# MainPSU.net
KiCad netlist of a schematic drawn in EAGLE
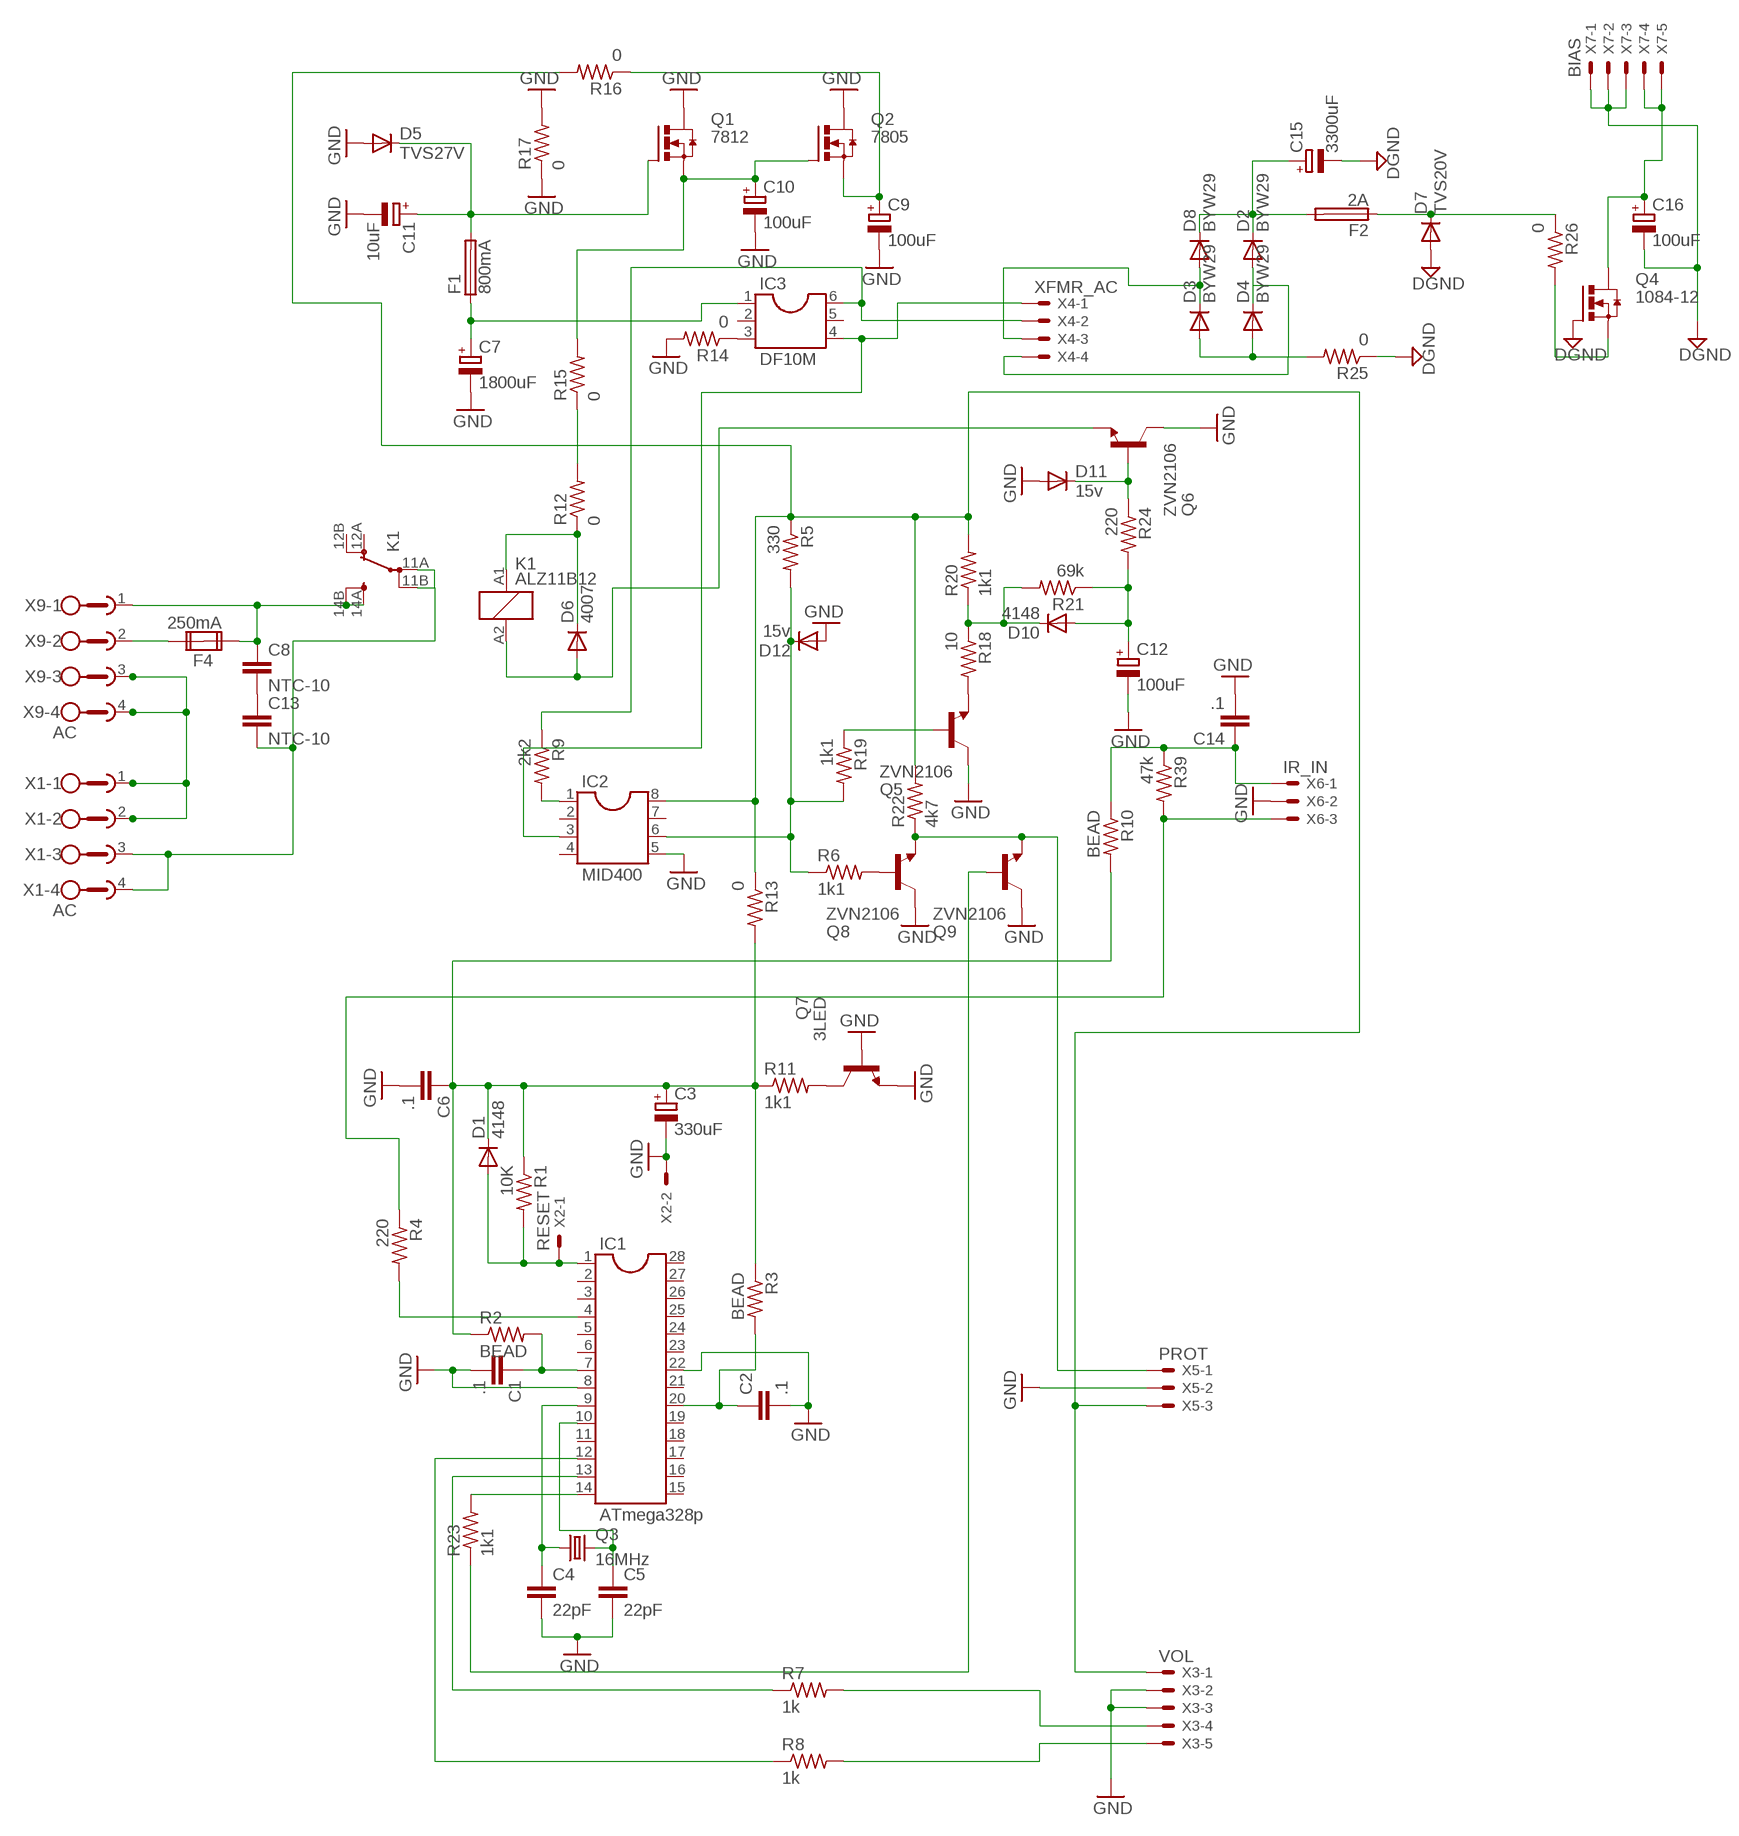
[diagram p0: schematic, sheet 1]

(export (version "E")
  (design (tool "Eeschema 10.0.6"))
  (components
    (comp (ref "C1")
      (value ".1")
      (footprint "eagle-import:C1210K")
      (libsource (lib "eagle-import") (part "C-EUC1210K"))
    )
    (comp (ref "C2")
      (value ".1")
      (footprint "eagle-import:C1210K")
      (libsource (lib "eagle-import") (part "C-EUC1210K"))
    )
    (comp (ref "C3")
      (value "330uF")
      (footprint "eagle-import:E3,5-10")
      (libsource (lib "eagle-import") (part "CPOL-EUE3.5-10"))
    )
    (comp (ref "C4")
      (value "22pF")
      (footprint "eagle-import:C1210K")
      (libsource (lib "eagle-import") (part "C-EUC1210K"))
    )
    (comp (ref "C5")
      (value "22pF")
      (footprint "eagle-import:C1210K")
      (libsource (lib "eagle-import") (part "C-EUC1210K"))
    )
    (comp (ref "C6")
      (value ".1")
      (footprint "eagle-import:C1210K")
      (libsource (lib "eagle-import") (part "C-EUC1210K"))
    )
    (comp (ref "C7")
      (value "1800uF")
      (footprint "eagle-import:E7,5-16")
      (libsource (lib "eagle-import") (part "CPOL-EUE7.5-16"))
    )
    (comp (ref "C8")
      (value "NTC-10")
      (footprint "eagle-import:C102-054X133")
      (libsource (lib "eagle-import") (part "C-EU102-054X133"))
    )
    (comp (ref "C9")
      (value "100uF")
      (footprint "eagle-import:E3,5-10")
      (libsource (lib "eagle-import") (part "CPOL-EUE3.5-10"))
    )
    (comp (ref "C10")
      (value "100uF")
      (footprint "eagle-import:E3,5-10")
      (libsource (lib "eagle-import") (part "CPOL-EUE3.5-10"))
    )
    (comp (ref "C11")
      (value "10uF")
      (footprint "eagle-import:E3,5-10")
      (libsource (lib "eagle-import") (part "CPOL-EUE3.5-10"))
    )
    (comp (ref "C12")
      (value "100uF")
      (footprint "eagle-import:E3,5-10")
      (libsource (lib "eagle-import") (part "CPOL-EUE3.5-10"))
    )
    (comp (ref "C13")
      (value "NTC-10")
      (footprint "eagle-import:C102-054X133")
      (libsource (lib "eagle-import") (part "C-EU102-054X133"))
    )
    (comp (ref "C14")
      (value ".1")
      (footprint "eagle-import:C1210K")
      (libsource (lib "eagle-import") (part "C-EUC1210K"))
    )
    (comp (ref "C15")
      (value "3300uF")
      (footprint "eagle-import:E7,5-16")
      (libsource (lib "eagle-import") (part "CPOL-EUE7.5-16"))
    )
    (comp (ref "C16")
      (value "100uF")
      (footprint "eagle-import:E3,5-10")
      (libsource (lib "eagle-import") (part "CPOL-EUE3.5-10"))
    )
    (comp (ref "D1")
      (value "4148")
      (footprint "eagle-import:DO35-7")
      (libsource (lib "eagle-import") (part "1N4148DO35-7"))
    )
    (comp (ref "D2")
      (value "BYW29")
      (footprint "eagle-import:DO220S")
      (libsource (lib "eagle-import") (part "BYW29"))
    )
    (comp (ref "D3")
      (value "BYW29")
      (footprint "eagle-import:DO220S")
      (libsource (lib "eagle-import") (part "BYW29"))
    )
    (comp (ref "D4")
      (value "BYW29")
      (footprint "eagle-import:DO220S")
      (libsource (lib "eagle-import") (part "BYW29"))
    )
    (comp (ref "D5")
      (value "TVS27V")
      (footprint "eagle-import:SOD57-10")
      (libsource (lib "eagle-import") (part "BY448"))
    )
    (comp (ref "D6")
      (value "4007")
      (footprint "eagle-import:DO41-10")
      (libsource (lib "eagle-import") (part "1N4004"))
    )
    (comp (ref "D7")
      (value "TVS20V")
      (footprint "eagle-import:SOD57-10")
      (libsource (lib "eagle-import") (part "BY448"))
    )
    (comp (ref "D8")
      (value "BYW29")
      (footprint "eagle-import:DO220S")
      (libsource (lib "eagle-import") (part "BYW29"))
    )
    (comp (ref "D10")
      (value "4148")
      (footprint "eagle-import:DO35-10")
      (libsource (lib "eagle-import") (part "1N4148DO35-10"))
    )
    (comp (ref "D11")
      (value "15v")
      (footprint "eagle-import:DO35-7")
      (libsource (lib "eagle-import") (part "1N4148DO35-7"))
    )
    (comp (ref "D12")
      (value "15v")
      (footprint "eagle-import:DO35-7")
      (libsource (lib "eagle-import") (part "1N4148DO35-7"))
    )
    (comp (ref "F1")
      (value "800mA")
      (footprint "eagle-import:19560")
      (fields (field (name "MPN") "56000001009"))
      (libsource (lib "eagle-import") (part "19560"))
    )
    (comp (ref "F2")
      (value "2A")
      (footprint "eagle-import:19560")
      (fields (field (name "MPN") "56000001009"))
      (libsource (lib "eagle-import") (part "19560"))
    )
    (comp (ref "F4")
      (value "250mA")
      (footprint "eagle-import:FUSE1")
      (libsource (lib "eagle-import") (part "FUSE2P"))
    )
    (comp (ref "IC1")
      (value "ATmega328p")
      (footprint "eagle-import:DIL28-3")
      (libsource (lib "eagle-import") (part "DIL28-3"))
    )
    (comp (ref "IC2")
      (value "MID400")
      (footprint "eagle-import:DIL08")
      (libsource (lib "eagle-import") (part "DIL8"))
    )
    (comp (ref "IC3")
      (value "DF10M")
      (footprint "eagle-import:DIL06")
      (libsource (lib "eagle-import") (part "DIL6"))
    )
    (comp (ref "K1")
      (value "ALZ11B12")
      (footprint "eagle-import:RT-C_O16A5")
      (fields (field (name "MPN") "RT314730"))
      (libsource (lib "eagle-import") (part "RT314730"))
    )
    (comp (ref "Q1")
      (value "7812")
      (footprint "eagle-import:TO220BH")
      (libsource (lib "eagle-import") (part "IRFI540NPBF"))
    )
    (comp (ref "Q2")
      (value "7805")
      (footprint "eagle-import:TO220BH")
      (libsource (lib "eagle-import") (part "IRFI540NPBF"))
    )
    (comp (ref "Q3")
      (value "16MHz")
      (footprint "eagle-import:HC49_S")
      (libsource (lib "eagle-import") (part "CRYSTALHC49S"))
    )
    (comp (ref "Q4")
      (value "1084-12")
      (footprint "eagle-import:TO220BH")
      (libsource (lib "eagle-import") (part "IRFI540NPBF"))
    )
    (comp (ref "Q5")
      (value "ZVN2106")
      (footprint "eagle-import:TO92-EBC")
      (libsource (lib "eagle-import") (part "BC550B"))
    )
    (comp (ref "Q6")
      (value "ZVN2106")
      (footprint "eagle-import:TO92-EBC")
      (libsource (lib "eagle-import") (part "BC550B"))
    )
    (comp (ref "Q7")
      (value "3LED")
      (footprint "eagle-import:TO92-EBC")
      (libsource (lib "eagle-import") (part "BC546A"))
    )
    (comp (ref "Q8")
      (value "ZVN2106")
      (footprint "eagle-import:TO92-EBC")
      (libsource (lib "eagle-import") (part "BC550B"))
    )
    (comp (ref "Q9")
      (value "ZVN2106")
      (footprint "eagle-import:TO92-EBC")
      (libsource (lib "eagle-import") (part "BC550B"))
    )
    (comp (ref "R1")
      (value "10K")
      (footprint "eagle-import:0309_10")
      (libsource (lib "eagle-import") (part "R-US_0309/10"))
    )
    (comp (ref "R2")
      (value "BEAD")
      (footprint "eagle-import:0309_10")
      (libsource (lib "eagle-import") (part "R-US_0309/10"))
    )
    (comp (ref "R3")
      (value "BEAD")
      (footprint "eagle-import:0309_12")
      (libsource (lib "eagle-import") (part "R-US_0309/12"))
    )
    (comp (ref "R4")
      (value "220")
      (footprint "eagle-import:0309_12")
      (libsource (lib "eagle-import") (part "R-US_0309/12"))
    )
    (comp (ref "R5")
      (value "330")
      (footprint "eagle-import:0309_10")
      (libsource (lib "eagle-import") (part "R-US_0309/10"))
    )
    (comp (ref "R6")
      (value "1k1")
      (footprint "eagle-import:0309_12")
      (libsource (lib "eagle-import") (part "R-US_0309/12"))
    )
    (comp (ref "R7")
      (value "1k")
      (footprint "eagle-import:R1210")
      (libsource (lib "eagle-import") (part "R-US_R1210"))
    )
    (comp (ref "R8")
      (value "1k")
      (footprint "eagle-import:R1210")
      (libsource (lib "eagle-import") (part "R-US_R1210"))
    )
    (comp (ref "R9")
      (value "2k2")
      (footprint "eagle-import:0309_12")
      (libsource (lib "eagle-import") (part "R-US_0309/12"))
    )
    (comp (ref "R10")
      (value "BEAD")
      (footprint "eagle-import:0309_10")
      (libsource (lib "eagle-import") (part "R-US_0309/10"))
    )
    (comp (ref "R11")
      (value "1k1")
      (footprint "eagle-import:0309_10")
      (libsource (lib "eagle-import") (part "R-US_0309/10"))
    )
    (comp (ref "R12")
      (value "0")
      (footprint "eagle-import:0309_10")
      (libsource (lib "eagle-import") (part "R-US_0309/10"))
    )
    (comp (ref "R13")
      (value "0")
      (footprint "eagle-import:0309_12")
      (libsource (lib "eagle-import") (part "R-US_0309/12"))
    )
    (comp (ref "R14")
      (value "0")
      (footprint "eagle-import:0309_10")
      (libsource (lib "eagle-import") (part "R-US_0309/10"))
    )
    (comp (ref "R15")
      (value "0")
      (footprint "eagle-import:0309_12")
      (libsource (lib "eagle-import") (part "R-US_0309/12"))
    )
    (comp (ref "R16")
      (value "0")
      (footprint "eagle-import:0309_12")
      (libsource (lib "eagle-import") (part "R-US_0309/12"))
    )
    (comp (ref "R17")
      (value "0")
      (footprint "eagle-import:0309_12")
      (libsource (lib "eagle-import") (part "R-US_0309/12"))
    )
    (comp (ref "R18")
      (value "10")
      (footprint "eagle-import:0207_5V")
      (libsource (lib "eagle-import") (part "R-US_0207/5V"))
    )
    (comp (ref "R19")
      (value "1k1")
      (footprint "eagle-import:0309_12")
      (libsource (lib "eagle-import") (part "R-US_0309/12"))
    )
    (comp (ref "R20")
      (value "1k1")
      (footprint "eagle-import:0309_10")
      (libsource (lib "eagle-import") (part "R-US_0309/10"))
    )
    (comp (ref "R21")
      (value "69k")
      (footprint "eagle-import:0309_10")
      (libsource (lib "eagle-import") (part "R-US_0309/10"))
    )
    (comp (ref "R22")
      (value "4k7")
      (footprint "eagle-import:0309_10")
      (libsource (lib "eagle-import") (part "R-US_0309/10"))
    )
    (comp (ref "R23")
      (value "1k1")
      (footprint "eagle-import:R1210")
      (libsource (lib "eagle-import") (part "R-US_R1210"))
    )
    (comp (ref "R24")
      (value "220")
      (footprint "eagle-import:0309_10")
      (libsource (lib "eagle-import") (part "R-US_0309/10"))
    )
    (comp (ref "R25")
      (value "0")
      (footprint "eagle-import:0309_12")
      (libsource (lib "eagle-import") (part "R-US_0309/12"))
    )
    (comp (ref "R26")
      (value "0")
      (footprint "eagle-import:0309_12")
      (libsource (lib "eagle-import") (part "R-US_0309/12"))
    )
    (comp (ref "R39")
      (value "47k")
      (footprint "eagle-import:0309_10")
      (libsource (lib "eagle-import") (part "R-US_0309/10"))
    )
    (comp (ref "X1")
      (value "AC")
      (footprint "eagle-import:GMSTBA4")
      (fields (field (name "MF") "FARNELL") (field (name "MPN") "1757268"))
      (libsource (lib "eagle-import") (part "GMSTBA4"))
    )
    (comp (ref "X2")
      (value "RESET")
      (footprint "eagle-import:22-23-2021")
      (fields (field (name "MF") "MOLEX") (field (name "MPN") "22-23-2021"))
      (libsource (lib "eagle-import") (part "22-23-2021"))
    )
    (comp (ref "X3")
      (value "VOL")
      (footprint "eagle-import:22-23-2051")
      (fields (field (name "MF") "MOLEX") (field (name "MPN") "22-23-2051"))
      (libsource (lib "eagle-import") (part "22-23-2051"))
    )
    (comp (ref "X4")
      (value "XFMR_AC")
      (footprint "eagle-import:5566-4")
      (libsource (lib "eagle-import") (part "5566-4"))
    )
    (comp (ref "X5")
      (value "PROT")
      (footprint "eagle-import:22-23-2031")
      (fields (field (name "MF") "MOLEX") (field (name "MPN") "22-23-2031"))
      (libsource (lib "eagle-import") (part "22-23-2031"))
    )
    (comp (ref "X6")
      (value "IR_IN")
      (footprint "eagle-import:22-23-2031")
      (fields (field (name "MF") "MOLEX") (field (name "MPN") "22-23-2031"))
      (libsource (lib "eagle-import") (part "22-23-2031"))
    )
    (comp (ref "X7")
      (value "BIAS")
      (footprint "eagle-import:22-23-2051")
      (fields (field (name "MF") "MOLEX") (field (name "MPN") "22-23-2051"))
      (libsource (lib "eagle-import") (part "22-23-2051"))
    )
    (comp (ref "X9")
      (value "AC")
      (footprint "eagle-import:GMSTBA4")
      (fields (field (name "MF") "FARNELL") (field (name "MPN") "1757268"))
      (libsource (lib "eagle-import") (part "GMSTBA4"))
    )
  )
  (nets
    (net (code "1") (name "DGND") (class "Default")
      (node (ref "C15") (pin "-") (pinfunction "-_-") (pintype "passive"))
      (node (ref "C16") (pin "-") (pinfunction "-_-") (pintype "passive"))
      (node (ref "D7") (pin "A") (pinfunction "A_A") (pintype "passive"))
      (node (ref "Q4") (pin "G") (pinfunction "G_G") (pintype "passive"))
      (node (ref "R25") (pin "1") (pinfunction "1_1") (pintype "passive"))
      (node (ref "X7") (pin "1") (pinfunction "S_1") (pintype "passive"))
      (node (ref "X7") (pin "2") (pinfunction "S_2") (pintype "passive"))
      (node (ref "X7") (pin "3") (pinfunction "S_3") (pintype "passive"))
    )
    (net (code "2") (name "GND") (class "Default")
      (node (ref "C1") (pin "2") (pinfunction "2_2") (pintype "passive"))
      (node (ref "C10") (pin "-") (pinfunction "-_-") (pintype "passive"))
      (node (ref "C11") (pin "-") (pinfunction "-_-") (pintype "passive"))
      (node (ref "C12") (pin "-") (pinfunction "-_-") (pintype "passive"))
      (node (ref "C14") (pin "2") (pinfunction "2_2") (pintype "passive"))
      (node (ref "C2") (pin "2") (pinfunction "2_2") (pintype "passive"))
      (node (ref "C3") (pin "-") (pinfunction "-_-") (pintype "passive"))
      (node (ref "C4") (pin "2") (pinfunction "2_2") (pintype "passive"))
      (node (ref "C5") (pin "2") (pinfunction "2_2") (pintype "passive"))
      (node (ref "C6") (pin "2") (pinfunction "2_2") (pintype "passive"))
      (node (ref "C7") (pin "-") (pinfunction "-_-") (pintype "passive"))
      (node (ref "C9") (pin "-") (pinfunction "-_-") (pintype "passive"))
      (node (ref "D11") (pin "A") (pinfunction "A_A") (pintype "passive"))
      (node (ref "D12") (pin "A") (pinfunction "A_A") (pintype "passive"))
      (node (ref "D5") (pin "A") (pinfunction "A_A") (pintype "passive"))
      (node (ref "IC1") (pin "22") (pinfunction "22_22") (pintype "passive"))
      (node (ref "IC1") (pin "8") (pinfunction "8_8") (pintype "passive"))
      (node (ref "IC2") (pin "5") (pinfunction "5_5") (pintype "passive"))
      (node (ref "Q1") (pin "D") (pinfunction "D_D") (pintype "passive"))
      (node (ref "Q2") (pin "D") (pinfunction "D_D") (pintype "passive"))
      (node (ref "Q5") (pin "C") (pinfunction "C_C") (pintype "passive"))
      (node (ref "Q6") (pin "C") (pinfunction "C_C") (pintype "passive"))
      (node (ref "Q7") (pin "B") (pinfunction "B_B") (pintype "passive"))
      (node (ref "Q7") (pin "E") (pinfunction "E_E") (pintype "passive"))
      (node (ref "Q8") (pin "C") (pinfunction "C_C") (pintype "passive"))
      (node (ref "Q9") (pin "C") (pinfunction "C_C") (pintype "passive"))
      (node (ref "R14") (pin "2") (pinfunction "2_2") (pintype "passive"))
      (node (ref "R17") (pin "1") (pinfunction "1_1") (pintype "passive"))
      (node (ref "R17") (pin "2") (pinfunction "2_2") (pintype "passive"))
      (node (ref "X2") (pin "2") (pinfunction "S_2") (pintype "passive"))
      (node (ref "X3") (pin "2") (pinfunction "S_2") (pintype "passive"))
      (node (ref "X3") (pin "3") (pinfunction "S_3") (pintype "passive"))
      (node (ref "X5") (pin "2") (pinfunction "S_2") (pintype "passive"))
      (node (ref "X6") (pin "2") (pinfunction "S_2") (pintype "passive"))
    )
    (net (code "3") (name "Net-(C1-Pad1)") (class "Default")
      (node (ref "C1") (pin "1") (pinfunction "1_1") (pintype "passive"))
      (node (ref "IC1") (pin "7") (pinfunction "7_7") (pintype "passive"))
      (node (ref "R2") (pin "2") (pinfunction "2_2") (pintype "passive"))
    )
    (net (code "4") (name "Net-(C2-Pad1)") (class "Default")
      (node (ref "C2") (pin "1") (pinfunction "1_1") (pintype "passive"))
      (node (ref "IC1") (pin "20") (pinfunction "20_20") (pintype "passive"))
      (node (ref "R3") (pin "2") (pinfunction "2_2") (pintype "passive"))
    )
    (net (code "5") (name "Net-(C3-Pad+)") (class "Default")
      (node (ref "C3") (pin "+") (pinfunction "+_+") (pintype "passive"))
      (node (ref "C6") (pin "1") (pinfunction "1_1") (pintype "passive"))
      (node (ref "D1") (pin "C") (pinfunction "C_C") (pintype "passive"))
      (node (ref "R1") (pin "1") (pinfunction "1_1") (pintype "passive"))
      (node (ref "R10") (pin "2") (pinfunction "2_2") (pintype "passive"))
      (node (ref "R11") (pin "1") (pinfunction "1_1") (pintype "passive"))
      (node (ref "R13") (pin "2") (pinfunction "2_2") (pintype "passive"))
      (node (ref "R2") (pin "1") (pinfunction "1_1") (pintype "passive"))
      (node (ref "R3") (pin "1") (pinfunction "1_1") (pintype "passive"))
    )
    (net (code "6") (name "Net-(C4-Pad1)") (class "Default")
      (node (ref "C4") (pin "1") (pinfunction "1_1") (pintype "passive"))
      (node (ref "IC1") (pin "9") (pinfunction "9_9") (pintype "passive"))
      (node (ref "Q3") (pin "1") (pinfunction "1_1") (pintype "passive"))
    )
    (net (code "7") (name "Net-(C5-Pad1)") (class "Default")
      (node (ref "C5") (pin "1") (pinfunction "1_1") (pintype "passive"))
      (node (ref "IC1") (pin "10") (pinfunction "10_10") (pintype "passive"))
      (node (ref "Q3") (pin "2") (pinfunction "2_2") (pintype "passive"))
    )
    (net (code "8") (name "Net-(C7-Pad+)") (class "Default")
      (node (ref "C7") (pin "+") (pinfunction "+_+") (pintype "passive"))
      (node (ref "F1") (pin "1") (pinfunction "1_1") (pintype "passive"))
      (node (ref "IC3") (pin "1") (pinfunction "1_1") (pintype "passive"))
    )
    (net (code "9") (name "Net-(C9-Pad+)") (class "Default")
      (node (ref "C9") (pin "+") (pinfunction "+_+") (pintype "passive"))
      (node (ref "Q2") (pin "S") (pinfunction "S_S") (pintype "passive"))
      (node (ref "R16") (pin "1") (pinfunction "1_1") (pintype "passive"))
    )
    (net (code "10") (name "Net-(C10-Pad+)") (class "Default")
      (node (ref "C10") (pin "+") (pinfunction "+_+") (pintype "passive"))
      (node (ref "Q1") (pin "S") (pinfunction "S_S") (pintype "passive"))
      (node (ref "Q2") (pin "G") (pinfunction "G_G") (pintype "passive"))
      (node (ref "R15") (pin "2") (pinfunction "2_2") (pintype "passive"))
    )
    (net (code "11") (name "Net-(C11-Pad+)") (class "Default")
      (node (ref "C11") (pin "+") (pinfunction "+_+") (pintype "passive"))
      (node (ref "D5") (pin "C") (pinfunction "C_C") (pintype "passive"))
      (node (ref "F1") (pin "2") (pinfunction "2_2") (pintype "passive"))
      (node (ref "Q1") (pin "G") (pinfunction "G_G") (pintype "passive"))
    )
    (net (code "12") (name "Net-(C12-Pad+)") (class "Default")
      (node (ref "C12") (pin "+") (pinfunction "+_+") (pintype "passive"))
      (node (ref "D10") (pin "A") (pinfunction "A_A") (pintype "passive"))
      (node (ref "R21") (pin "1") (pinfunction "1_1") (pintype "passive"))
      (node (ref "R24") (pin "2") (pinfunction "2_2") (pintype "passive"))
    )
    (net (code "13") (name "Net-(C13-Pad1)") (class "Default")
      (node (ref "C13") (pin "1") (pinfunction "1_1") (pintype "passive"))
      (node (ref "C8") (pin "2") (pinfunction "2_2") (pintype "passive"))
    )
    (net (code "14") (name "Net-(C15-Pad+)") (class "Default")
      (node (ref "C15") (pin "+") (pinfunction "+_+") (pintype "passive"))
      (node (ref "D2") (pin "C") (pinfunction "C_C") (pintype "passive"))
      (node (ref "D8") (pin "C") (pinfunction "C_C") (pintype "passive"))
      (node (ref "F2") (pin "2") (pinfunction "2_2") (pintype "passive"))
    )
    (net (code "15") (name "Net-(D3-PadA)") (class "Default")
      (node (ref "D3") (pin "A") (pinfunction "A_A") (pintype "passive"))
      (node (ref "D4") (pin "A") (pinfunction "A_A") (pintype "passive"))
      (node (ref "R25") (pin "2") (pinfunction "2_2") (pintype "passive"))
    )
    (net (code "16") (name "Net-(D7-PadC)") (class "Default")
      (node (ref "D7") (pin "C") (pinfunction "C_C") (pintype "passive"))
      (node (ref "F2") (pin "1") (pinfunction "1_1") (pintype "passive"))
      (node (ref "R26") (pin "1") (pinfunction "1_1") (pintype "passive"))
    )
    (net (code "17") (name "Net-(D10-PadC)") (class "Default")
      (node (ref "D10") (pin "C") (pinfunction "C_C") (pintype "passive"))
      (node (ref "R18") (pin "1") (pinfunction "1_1") (pintype "passive"))
      (node (ref "R20") (pin "1") (pinfunction "1_1") (pintype "passive"))
      (node (ref "R21") (pin "2") (pinfunction "2_2") (pintype "passive"))
    )
    (net (code "18") (name "Net-(D11-PadC)") (class "Default")
      (node (ref "D11") (pin "C") (pinfunction "C_C") (pintype "passive"))
      (node (ref "Q6") (pin "B") (pinfunction "B_B") (pintype "passive"))
      (node (ref "R24") (pin "1") (pinfunction "1_1") (pintype "passive"))
    )
    (net (code "19") (name "Net-(D12-PadC)") (class "Default")
      (node (ref "D12") (pin "C") (pinfunction "C_C") (pintype "passive"))
      (node (ref "IC2") (pin "6") (pinfunction "6_6") (pintype "passive"))
      (node (ref "R19") (pin "2") (pinfunction "2_2") (pintype "passive"))
      (node (ref "R5") (pin "2") (pinfunction "2_2") (pintype "passive"))
      (node (ref "R6") (pin "1") (pinfunction "1_1") (pintype "passive"))
    )
    (net (code "20") (name "Net-(IC1-Pad4)") (class "Default")
      (node (ref "IC1") (pin "4") (pinfunction "4_4") (pintype "passive"))
      (node (ref "R4") (pin "2") (pinfunction "2_2") (pintype "passive"))
    )
    (net (code "21") (name "Net-(IC1-Pad12)") (class "Default")
      (node (ref "IC1") (pin "12") (pinfunction "12_12") (pintype "passive"))
      (node (ref "R8") (pin "1") (pinfunction "1_1") (pintype "passive"))
    )
    (net (code "22") (name "Net-(IC1-Pad13)") (class "Default")
      (node (ref "IC1") (pin "13") (pinfunction "13_13") (pintype "passive"))
      (node (ref "R7") (pin "1") (pinfunction "1_1") (pintype "passive"))
    )
    (net (code "23") (name "Net-(IC1-Pad14)") (class "Default")
      (node (ref "IC1") (pin "14") (pinfunction "14_14") (pintype "passive"))
      (node (ref "R23") (pin "2") (pinfunction "2_2") (pintype "passive"))
    )
    (net (code "24") (name "Net-(IC2-Pad1)") (class "Default")
      (node (ref "IC2") (pin "1") (pinfunction "1_1") (pintype "passive"))
      (node (ref "R9") (pin "2") (pinfunction "2_2") (pintype "passive"))
    )
    (net (code "25") (name "Net-(IC3-Pad3)") (class "Default")
      (node (ref "IC3") (pin "3") (pinfunction "3_3") (pintype "passive"))
      (node (ref "R14") (pin "1") (pinfunction "1_1") (pintype "passive"))
    )
    (net (code "26") (name "Net-(K1A-1)") (class "Default")
      (node (ref "D6") (pin "C") (pinfunction "C_C") (pintype "passive"))
      (node (ref "K1") (pin "A1") (pinfunction "1_A1") (pintype "passive"))
      (node (ref "R12") (pin "1") (pinfunction "1_1") (pintype "passive"))
    )
    (net (code "27") (name "Net-(K1A-2)") (class "Default")
      (node (ref "D6") (pin "A") (pinfunction "A_A") (pintype "passive"))
      (node (ref "K1") (pin "A2") (pinfunction "2_A2") (pintype "passive"))
      (node (ref "Q6") (pin "E") (pinfunction "E_E") (pintype "passive"))
    )
    (net (code "28") (name "Net-(K1B-PA)") (class "Default")
      (node (ref "C13") (pin "2") (pinfunction "2_2") (pintype "passive"))
      (node (ref "K1") (pin "11A") (pinfunction "PA_11A") (pintype "passive"))
      (node (ref "K1") (pin "11B") (pinfunction "PB_11B") (pintype "passive"))
      (node (ref "X1") (pin "3") (pinfunction "1_3") (pintype "passive"))
      (node (ref "X1") (pin "4") (pinfunction "1_4") (pintype "passive"))
    )
    (net (code "29") (name "Net-(K1B-SA)") (class "Default")
      (node (ref "C8") (pin "1") (pinfunction "1_1") (pintype "passive"))
      (node (ref "F4") (pin "1A") (pinfunction "1A_1A") (pintype "passive"))
      (node (ref "K1") (pin "14A") (pinfunction "SA_14A") (pintype "passive"))
      (node (ref "K1") (pin "14B") (pinfunction "SB_14B") (pintype "passive"))
      (node (ref "X9") (pin "1") (pinfunction "1_1") (pintype "passive"))
    )
    (net (code "30") (name "Net-(Q4-PadS)") (class "Default")
      (node (ref "Q4") (pin "S") (pinfunction "S_S") (pintype "passive"))
      (node (ref "R26") (pin "2") (pinfunction "2_2") (pintype "passive"))
    )
    (net (code "31") (name "Net-(Q5-PadB)") (class "Default")
      (node (ref "Q5") (pin "B") (pinfunction "B_B") (pintype "passive"))
      (node (ref "R19") (pin "1") (pinfunction "1_1") (pintype "passive"))
    )
    (net (code "32") (name "Net-(Q5-PadE)") (class "Default")
      (node (ref "Q5") (pin "E") (pinfunction "E_E") (pintype "passive"))
      (node (ref "R18") (pin "2") (pinfunction "2_2") (pintype "passive"))
    )
    (net (code "33") (name "Net-(Q7-PadC)") (class "Default")
      (node (ref "Q7") (pin "C") (pinfunction "C_C") (pintype "passive"))
      (node (ref "R11") (pin "2") (pinfunction "2_2") (pintype "passive"))
    )
    (net (code "34") (name "Net-(Q8-PadB)") (class "Default")
      (node (ref "Q8") (pin "B") (pinfunction "B_B") (pintype "passive"))
      (node (ref "R6") (pin "2") (pinfunction "2_2") (pintype "passive"))
    )
    (net (code "35") (name "Net-(Q9-PadB)") (class "Default")
      (node (ref "Q9") (pin "B") (pinfunction "B_B") (pintype "passive"))
      (node (ref "R23") (pin "1") (pinfunction "1_1") (pintype "passive"))
    )
    (net (code "36") (name "Net-(R12-Pad2)") (class "Default")
      (node (ref "R12") (pin "2") (pinfunction "2_2") (pintype "passive"))
      (node (ref "R15") (pin "1") (pinfunction "1_1") (pintype "passive"))
    )
    (net (code "37") (name "Net-(X1B-1)") (class "Default")
      (node (ref "X1") (pin "1") (pinfunction "1_1") (pintype "passive"))
      (node (ref "X1") (pin "2") (pinfunction "1_2") (pintype "passive"))
      (node (ref "X9") (pin "3") (pinfunction "1_3") (pintype "passive"))
      (node (ref "X9") (pin "4") (pinfunction "1_4") (pintype "passive"))
    )
    (net (code "38") (name "Net-(X2A-S)") (class "Default")
      (node (ref "D1") (pin "A") (pinfunction "A_A") (pintype "passive"))
      (node (ref "IC1") (pin "1") (pinfunction "1_1") (pintype "passive"))
      (node (ref "R1") (pin "2") (pinfunction "2_2") (pintype "passive"))
      (node (ref "X2") (pin "1") (pinfunction "S_1") (pintype "passive"))
    )
    (net (code "39") (name "Net-(X3A-S)") (class "Default")
      (node (ref "IC2") (pin "8") (pinfunction "8_8") (pintype "passive"))
      (node (ref "R13") (pin "1") (pinfunction "1_1") (pintype "passive"))
      (node (ref "R16") (pin "2") (pinfunction "2_2") (pintype "passive"))
      (node (ref "R20") (pin "2") (pinfunction "2_2") (pintype "passive"))
      (node (ref "R22") (pin "2") (pinfunction "2_2") (pintype "passive"))
      (node (ref "R5") (pin "1") (pinfunction "1_1") (pintype "passive"))
      (node (ref "X3") (pin "1") (pinfunction "S_1") (pintype "passive"))
      (node (ref "X5") (pin "3") (pinfunction "S_3") (pintype "passive"))
    )
    (net (code "40") (name "Net-(X3D-S)") (class "Default")
      (node (ref "R7") (pin "2") (pinfunction "2_2") (pintype "passive"))
      (node (ref "X3") (pin "4") (pinfunction "S_4") (pintype "passive"))
    )
    (net (code "41") (name "Net-(X3E-S)") (class "Default")
      (node (ref "R8") (pin "2") (pinfunction "2_2") (pintype "passive"))
      (node (ref "X3") (pin "5") (pinfunction "S_5") (pintype "passive"))
    )
    (net (code "42") (name "Net-(X4A-S)") (class "Default")
      (node (ref "IC2") (pin "3") (pinfunction "3_3") (pintype "passive"))
      (node (ref "IC3") (pin "4") (pinfunction "4_4") (pintype "passive"))
      (node (ref "X4") (pin "1") (pinfunction "S_1") (pintype "passive"))
    )
    (net (code "43") (name "Net-(X4B-S)") (class "Default")
      (node (ref "IC3") (pin "6") (pinfunction "6_6") (pintype "passive"))
      (node (ref "R9") (pin "1") (pinfunction "1_1") (pintype "passive"))
      (node (ref "X4") (pin "2") (pinfunction "S_2") (pintype "passive"))
    )
    (net (code "44") (name "Net-(X4C-S)") (class "Default")
      (node (ref "D3") (pin "C") (pinfunction "C_C") (pintype "passive"))
      (node (ref "D8") (pin "A") (pinfunction "A_A") (pintype "passive"))
      (node (ref "X4") (pin "3") (pinfunction "S_3") (pintype "passive"))
    )
    (net (code "45") (name "Net-(X4D-S)") (class "Default")
      (node (ref "D2") (pin "A") (pinfunction "A_A") (pintype "passive"))
      (node (ref "D4") (pin "C") (pinfunction "C_C") (pintype "passive"))
      (node (ref "X4") (pin "4") (pinfunction "S_4") (pintype "passive"))
    )
    (net (code "46") (name "Net-(X5A-S)") (class "Default")
      (node (ref "Q8") (pin "E") (pinfunction "E_E") (pintype "passive"))
      (node (ref "Q9") (pin "E") (pinfunction "E_E") (pintype "passive"))
      (node (ref "R22") (pin "1") (pinfunction "1_1") (pintype "passive"))
      (node (ref "X5") (pin "1") (pinfunction "S_1") (pintype "passive"))
    )
    (net (code "47") (name "Net-(X6A-S)") (class "Default")
      (node (ref "C14") (pin "1") (pinfunction "1_1") (pintype "passive"))
      (node (ref "R10") (pin "1") (pinfunction "1_1") (pintype "passive"))
      (node (ref "R39") (pin "1") (pinfunction "1_1") (pintype "passive"))
      (node (ref "X6") (pin "1") (pinfunction "S_1") (pintype "passive"))
    )
    (net (code "48") (name "Net-(X6C-S)") (class "Default")
      (node (ref "R39") (pin "2") (pinfunction "2_2") (pintype "passive"))
      (node (ref "R4") (pin "1") (pinfunction "1_1") (pintype "passive"))
      (node (ref "X6") (pin "3") (pinfunction "S_3") (pintype "passive"))
    )
    (net (code "49") (name "Net-(X7D-S)") (class "Default")
      (node (ref "C16") (pin "+") (pinfunction "+_+") (pintype "passive"))
      (node (ref "Q4") (pin "D") (pinfunction "D_D") (pintype "passive"))
      (node (ref "X7") (pin "4") (pinfunction "S_4") (pintype "passive"))
      (node (ref "X7") (pin "5") (pinfunction "S_5") (pintype "passive"))
    )
    (net (code "50") (name "Net-(X9B-1)") (class "Default")
      (node (ref "F4") (pin "2A") (pinfunction "2A_2A") (pintype "passive"))
      (node (ref "X9") (pin "2") (pinfunction "1_2") (pintype "passive"))
    )
    (net (code "51") (name "unconnected-(F4-Pad1B)") (class "Default")
      (node (ref "F4") (pin "1B") (pinfunction "1B_1B") (pintype "passive"))
    )
    (net (code "52") (name "unconnected-(F4-Pad2B)") (class "Default")
      (node (ref "F4") (pin "2B") (pinfunction "2B_2B") (pintype "passive"))
    )
    (net (code "53") (name "unconnected-(IC1-Pad2)") (class "Default")
      (node (ref "IC1") (pin "2") (pinfunction "2_2") (pintype "passive"))
    )
    (net (code "54") (name "unconnected-(IC1-Pad3)") (class "Default")
      (node (ref "IC1") (pin "3") (pinfunction "3_3") (pintype "passive"))
    )
    (net (code "55") (name "unconnected-(IC1-Pad5)") (class "Default")
      (node (ref "IC1") (pin "5") (pinfunction "5_5") (pintype "passive"))
    )
    (net (code "56") (name "unconnected-(IC1-Pad6)") (class "Default")
      (node (ref "IC1") (pin "6") (pinfunction "6_6") (pintype "passive"))
    )
    (net (code "57") (name "unconnected-(IC1-Pad11)") (class "Default")
      (node (ref "IC1") (pin "11") (pinfunction "11_11") (pintype "passive"))
    )
    (net (code "58") (name "unconnected-(IC1-Pad15)") (class "Default")
      (node (ref "IC1") (pin "15") (pinfunction "15_15") (pintype "passive"))
    )
    (net (code "59") (name "unconnected-(IC1-Pad16)") (class "Default")
      (node (ref "IC1") (pin "16") (pinfunction "16_16") (pintype "passive"))
    )
    (net (code "60") (name "unconnected-(IC1-Pad17)") (class "Default")
      (node (ref "IC1") (pin "17") (pinfunction "17_17") (pintype "passive"))
    )
    (net (code "61") (name "unconnected-(IC1-Pad18)") (class "Default")
      (node (ref "IC1") (pin "18") (pinfunction "18_18") (pintype "passive"))
    )
    (net (code "62") (name "unconnected-(IC1-Pad19)") (class "Default")
      (node (ref "IC1") (pin "19") (pinfunction "19_19") (pintype "passive"))
    )
    (net (code "63") (name "unconnected-(IC1-Pad21)") (class "Default")
      (node (ref "IC1") (pin "21") (pinfunction "21_21") (pintype "passive"))
    )
    (net (code "64") (name "unconnected-(IC1-Pad23)") (class "Default")
      (node (ref "IC1") (pin "23") (pinfunction "23_23") (pintype "passive"))
    )
    (net (code "65") (name "unconnected-(IC1-Pad24)") (class "Default")
      (node (ref "IC1") (pin "24") (pinfunction "24_24") (pintype "passive"))
    )
    (net (code "66") (name "unconnected-(IC1-Pad25)") (class "Default")
      (node (ref "IC1") (pin "25") (pinfunction "25_25") (pintype "passive"))
    )
    (net (code "67") (name "unconnected-(IC1-Pad26)") (class "Default")
      (node (ref "IC1") (pin "26") (pinfunction "26_26") (pintype "passive"))
    )
    (net (code "68") (name "unconnected-(IC1-Pad27)") (class "Default")
      (node (ref "IC1") (pin "27") (pinfunction "27_27") (pintype "passive"))
    )
    (net (code "69") (name "unconnected-(IC1-Pad28)") (class "Default")
      (node (ref "IC1") (pin "28") (pinfunction "28_28") (pintype "passive"))
    )
    (net (code "70") (name "unconnected-(IC2-Pad2)") (class "Default")
      (node (ref "IC2") (pin "2") (pinfunction "2_2") (pintype "passive"))
    )
    (net (code "71") (name "unconnected-(IC2-Pad4)") (class "Default")
      (node (ref "IC2") (pin "4") (pinfunction "4_4") (pintype "passive"))
    )
    (net (code "72") (name "unconnected-(IC2-Pad7)") (class "Default")
      (node (ref "IC2") (pin "7") (pinfunction "7_7") (pintype "passive"))
    )
    (net (code "73") (name "unconnected-(IC3-Pad2)") (class "Default")
      (node (ref "IC3") (pin "2") (pinfunction "2_2") (pintype "passive"))
    )
    (net (code "74") (name "unconnected-(IC3-Pad5)") (class "Default")
      (node (ref "IC3") (pin "5") (pinfunction "5_5") (pintype "passive"))
    )
    (net (code "75") (name "unconnected-(K1B-OA-Pad12A)") (class "Default")
      (node (ref "K1") (pin "12A") (pinfunction "OA_12A") (pintype "passive"))
    )
    (net (code "76") (name "unconnected-(K1B-OB-Pad12B)") (class "Default")
      (node (ref "K1") (pin "12B") (pinfunction "OB_12B") (pintype "passive"))
    )
  )
)
